# SCH_ESP32-S3-WROOM-RadioGateway-v1_0_202.net
KiCad netlist of a schematic drawn in EasyEDA
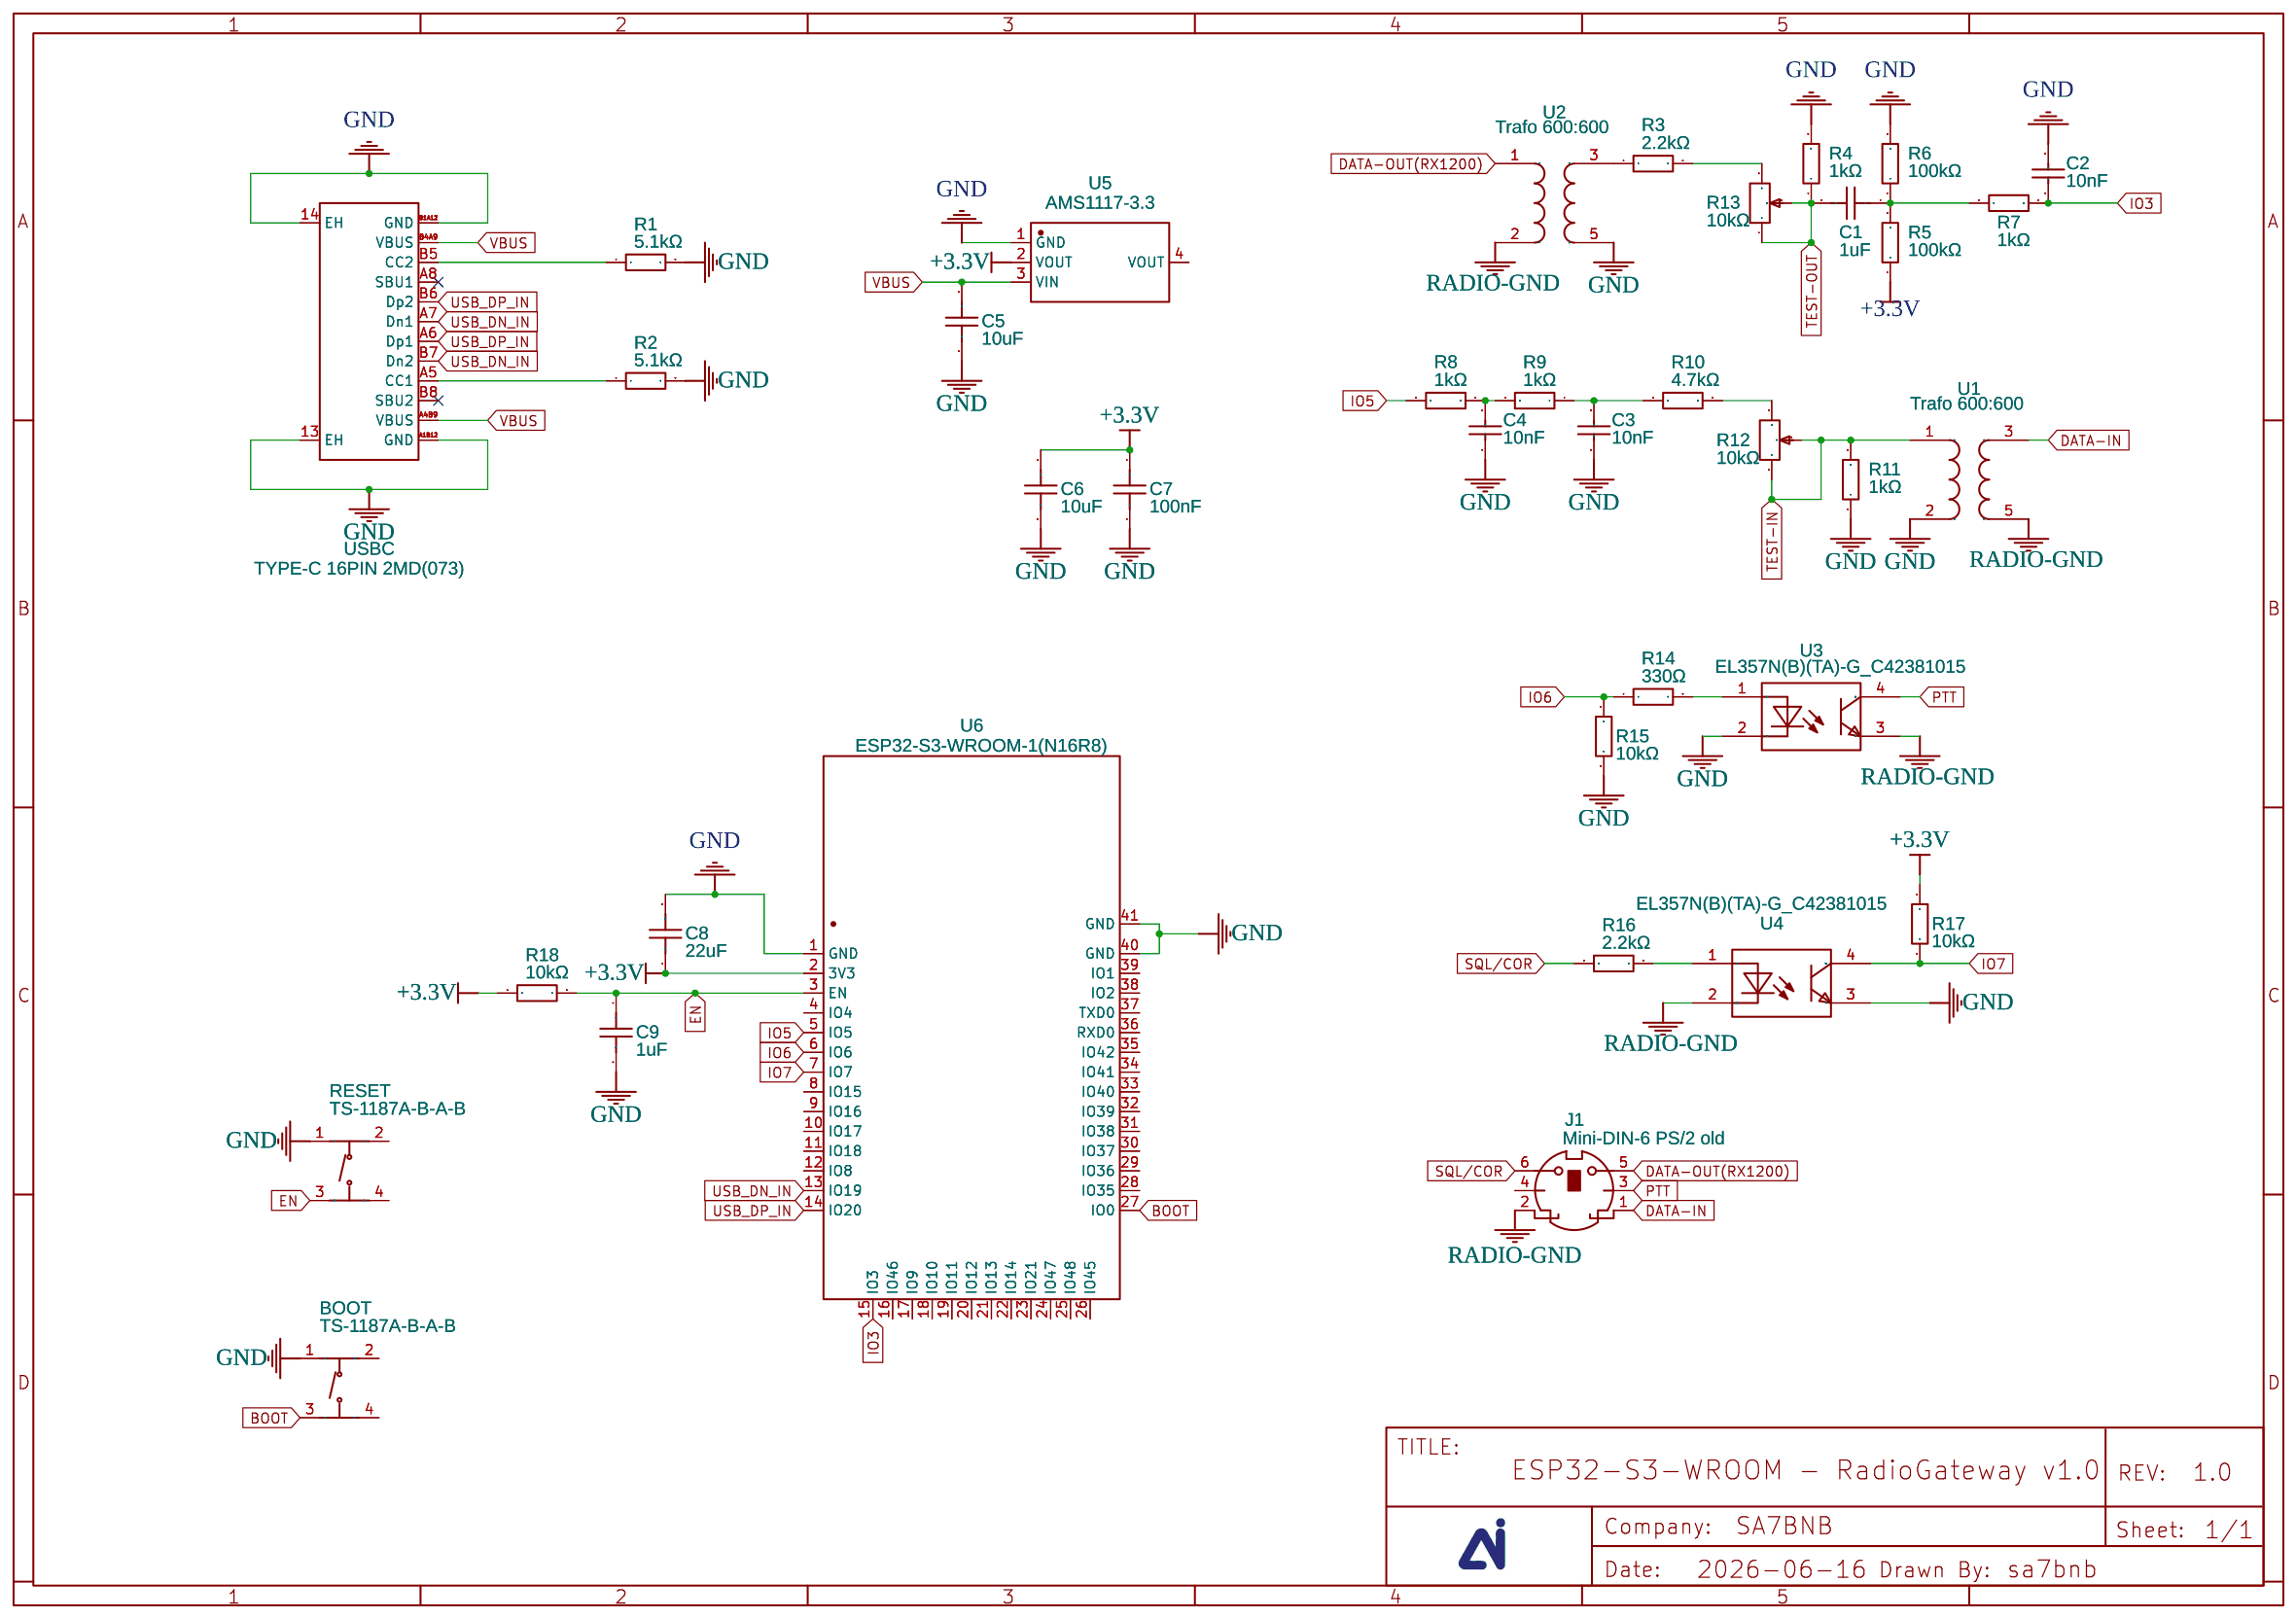
[diagram p0: schematic sheet]

(export (version "E")
  (design (tool "Eeschema 10.0.6"))
  (components
    (comp (ref "BOOT")
      (value "TS-1187A-B-A-B")
      (fields (field (name "Manufacturer") "XKB Connection(中国星坤)"))
      (libsource (lib "") (part "TS-1187A-B-A-B"))
    )
    (comp (ref "C1")
      (value "1uF")
      (fields
        (field (name "Manufacturer Part") "CL05A105KA5NQNC")
        (field (name "Manufacturer") "SAMSUNG(三星)")
      )
      (libsource (lib "") (part "CL05A105KA5NQNC"))
    )
    (comp (ref "C2")
      (value "10nF")
      (fields
        (field (name "Manufacturer Part") "CL05B103KB5NNNC")
        (field (name "Manufacturer") "SAMSUNG(三星)")
      )
      (libsource (lib "") (part "CL05B103KB5NNNC"))
    )
    (comp (ref "C3")
      (value "10nF")
      (fields
        (field (name "Manufacturer Part") "CL05B103KB5NNNC")
        (field (name "Manufacturer") "SAMSUNG(三星)")
      )
      (libsource (lib "") (part "CL05B103KB5NNNC"))
    )
    (comp (ref "C4")
      (value "10nF")
      (fields
        (field (name "Manufacturer Part") "CL05B103KB5NNNC")
        (field (name "Manufacturer") "SAMSUNG(三星)")
      )
      (libsource (lib "") (part "CL05B103KB5NNNC"))
    )
    (comp (ref "C5")
      (value "10uF")
      (fields
        (field (name "Manufacturer Part") "CL10A106KP8NNNC")
        (field (name "Manufacturer") "SAMSUNG(三星)")
      )
      (libsource (lib "") (part "CL10A106KP8NNNC_1"))
    )
    (comp (ref "C6")
      (value "10uF")
      (fields
        (field (name "Manufacturer Part") "CL10A106KP8NNNC")
        (field (name "Manufacturer") "SAMSUNG(三星)")
      )
      (libsource (lib "") (part "CL10A106KP8NNNC"))
    )
    (comp (ref "C7")
      (value "100nF")
      (fields
        (field (name "Manufacturer Part") "CL05B104KO5NNNC")
        (field (name "Manufacturer") "SAMSUNG(三星)")
      )
      (libsource (lib "") (part "CL05B104KO5NNNC"))
    )
    (comp (ref "C8")
      (value "22uF")
      (fields
        (field (name "Manufacturer Part") "CL21A226MAQNNNE")
        (field (name "Manufacturer") "SAMSUNG(三星)")
      )
      (libsource (lib "") (part "CL21A226MAQNNNE"))
    )
    (comp (ref "C9")
      (value "1uF")
      (fields
        (field (name "Manufacturer Part") "CL05A105KA5NQNC")
        (field (name "Manufacturer") "SAMSUNG(三星)")
      )
      (libsource (lib "") (part "CL05A105KA5NQNC_1"))
    )
    (comp (ref "J1") (value "Mini-DIN-6 PS/2 old") (libsource (lib "") (part "Mini-DIN-6 PS/2 old")))
    (comp (ref "R1")
      (value "5.1kΩ")
      (fields
        (field (name "Manufacturer Part") "0402WGF5101TCE")
        (field (name "Manufacturer") "UNI-ROYAL(厚声)")
      )
      (libsource (lib "") (part "0402WGF5101TCE"))
    )
    (comp (ref "R2")
      (value "5.1kΩ")
      (fields
        (field (name "Manufacturer Part") "0402WGF5101TCE")
        (field (name "Manufacturer") "UNI-ROYAL(厚声)")
      )
      (libsource (lib "") (part "0402WGF5101TCE"))
    )
    (comp (ref "R3")
      (value "2.2kΩ")
      (fields
        (field (name "Manufacturer Part") "0402WGF2201TCE")
        (field (name "Manufacturer") "UNI-ROYAL(厚声)")
      )
      (libsource (lib "") (part "0402WGF2201TCE"))
    )
    (comp (ref "R4")
      (value "1kΩ")
      (fields
        (field (name "Manufacturer Part") "0402WGF1001TCE")
        (field (name "Manufacturer") "UNI-ROYAL(厚声)")
      )
      (libsource (lib "") (part "0402WGF1001TCE_2"))
    )
    (comp (ref "R5")
      (value "100kΩ")
      (fields
        (field (name "Manufacturer Part") "0402WGF1003TCE")
        (field (name "Manufacturer") "UNI-ROYAL(厚声)")
      )
      (libsource (lib "") (part "0402WGF1003TCE"))
    )
    (comp (ref "R6")
      (value "100kΩ")
      (fields
        (field (name "Manufacturer Part") "0402WGF1003TCE")
        (field (name "Manufacturer") "UNI-ROYAL(厚声)")
      )
      (libsource (lib "") (part "0402WGF1003TCE"))
    )
    (comp (ref "R7")
      (value "1kΩ")
      (fields
        (field (name "Manufacturer Part") "0402WGF1001TCE")
        (field (name "Manufacturer") "UNI-ROYAL(厚声)")
      )
      (libsource (lib "") (part "0402WGF1001TCE_1"))
    )
    (comp (ref "R8")
      (value "1kΩ")
      (fields
        (field (name "Manufacturer Part") "0402WGF1001TCE")
        (field (name "Manufacturer") "UNI-ROYAL(厚声)")
      )
      (libsource (lib "") (part "0402WGF1001TCE"))
    )
    (comp (ref "R9")
      (value "1kΩ")
      (fields
        (field (name "Manufacturer Part") "0402WGF1001TCE")
        (field (name "Manufacturer") "UNI-ROYAL(厚声)")
      )
      (libsource (lib "") (part "0402WGF1001TCE"))
    )
    (comp (ref "R10")
      (value "4.7kΩ")
      (fields
        (field (name "Manufacturer Part") "0402WGF4701TCE")
        (field (name "Manufacturer") "UNI-ROYAL(厚声)")
      )
      (libsource (lib "") (part "0402WGF4701TCE"))
    )
    (comp (ref "R11")
      (value "1kΩ")
      (fields
        (field (name "Manufacturer Part") "0402WGF1001TCE")
        (field (name "Manufacturer") "UNI-ROYAL(厚声)")
      )
      (libsource (lib "") (part "0402WGF1001TCE_2"))
    )
    (comp (ref "R12")
      (value "10kΩ")
      (fields (field (name "Manufacturer Part") "3296W-1-103LF") (field (name "Manufacturer") "BOURNS"))
      (libsource (lib "") (part "3296W-1-103LF"))
    )
    (comp (ref "R13")
      (value "10kΩ")
      (fields (field (name "Manufacturer Part") "3296W-1-103LF") (field (name "Manufacturer") "BOURNS"))
      (libsource (lib "") (part "3296W-1-103LF"))
    )
    (comp (ref "R14")
      (value "330Ω")
      (fields
        (field (name "Manufacturer Part") "0402WGF3300TCE")
        (field (name "Manufacturer") "UNI-ROYAL(厚声)")
      )
      (libsource (lib "") (part "0402WGF3300TCE"))
    )
    (comp (ref "R15")
      (value "10kΩ")
      (fields
        (field (name "Manufacturer Part") "0402WGF1002TCE")
        (field (name "Manufacturer") "UNI-ROYAL(厚声)")
      )
      (libsource (lib "") (part "0402WGF1002TCE"))
    )
    (comp (ref "R16")
      (value "2.2kΩ")
      (fields
        (field (name "Manufacturer Part") "0402WGF2201TCE")
        (field (name "Manufacturer") "UNI-ROYAL(厚声)")
      )
      (libsource (lib "") (part "0402WGF2201TCE"))
    )
    (comp (ref "R17")
      (value "10kΩ")
      (fields
        (field (name "Manufacturer Part") "0402WGF1002TCE")
        (field (name "Manufacturer") "UNI-ROYAL(厚声)")
      )
      (libsource (lib "") (part "0402WGF1002TCE"))
    )
    (comp (ref "R18")
      (value "10kΩ")
      (fields
        (field (name "Manufacturer Part") "0402WGF1002TCE")
        (field (name "Manufacturer") "UNI-ROYAL(厚声)")
      )
      (libsource (lib "") (part "0402WGF1002TCE_1"))
    )
    (comp (ref "RESET")
      (value "TS-1187A-B-A-B")
      (fields (field (name "Manufacturer") "XKB Connection(中国星坤)"))
      (libsource (lib "") (part "TS-1187A-B-A-B_1"))
    )
    (comp (ref "U1")
      (value "Trafo 600:600")
      (fields (field (name "Manufacturer") "YongYeTai"))
      (libsource (lib "") (part "eduardo"))
    )
    (comp (ref "U2")
      (value "Trafo 600:600")
      (fields (field (name "Manufacturer") "YongYeTai"))
      (libsource (lib "") (part "eduardo"))
    )
    (comp (ref "U3")
      (value "EL357N(B)(TA)-G_C42381015")
      (fields
        (field (name "Manufacturer Part") "EL357N(B)(TA)-G")
        (field (name "Manufacturer") "EVERLIGHT(亿光)")
      )
      (libsource (lib "") (part "EL357N(B)(TA)-G_C42381015"))
    )
    (comp (ref "U4")
      (value "EL357N(B)(TA)-G_C42381015")
      (fields
        (field (name "Manufacturer Part") "EL357N(B)(TA)-G")
        (field (name "Manufacturer") "EVERLIGHT(亿光)")
      )
      (libsource (lib "") (part "EL357N(B)(TA)-G_C42381015"))
    )
    (comp (ref "U5")
      (value "AMS1117-3.3")
      (fields (field (name "Manufacturer") "Advanced Monolithic Systems"))
      (libsource (lib "") (part "AMS1117-3.3"))
    )
    (comp (ref "U6")
      (value "ESP32-S3-WROOM-1(N16R8)")
      (fields
        (field (name "Manufacturer Part") "ESP32-S3-WROOM-1-N16R8")
        (field (name "Manufacturer") "ESPRESSIF(乐鑫)")
      )
      (libsource (lib "") (part "ESP32-S3-WROOM-1(N16R8)"))
    )
    (comp (ref "USBC")
      (value "TYPE-C 16PIN 2MD(073)")
      (fields (field (name "Manufacturer") "SHOU HAN(首韩)"))
      (libsource (lib "") (part "TYPE-C 16PIN 2MD(073)"))
    )
  )
  (nets
    (net (code "1") (name "+3.3V") (class "Default")
      (node (ref "C6") (pin "1") (pinfunction "1_1") (pintype "unspecified"))
      (node (ref "C7") (pin "1") (pinfunction "1_1") (pintype "unspecified"))
      (node (ref "C8") (pin "1") (pinfunction "1_1") (pintype "unspecified"))
      (node (ref "R17") (pin "1") (pinfunction "1_1") (pintype "input"))
      (node (ref "R18") (pin "1") (pinfunction "1_1") (pintype "input"))
      (node (ref "R5") (pin "1") (pinfunction "1_1") (pintype "input"))
      (node (ref "U5") (pin "2") (pinfunction "VOUT_2") (pintype "unspecified"))
      (node (ref "U6") (pin "2") (pinfunction "3V3_2") (pintype "unspecified"))
    )
    (net (code "2") (name "BOOT") (class "Default")
      (node (ref "BOOT") (pin "3") (pinfunction "C_3") (pintype "unspecified"))
      (node (ref "U6") (pin "27") (pinfunction "IO0_27") (pintype "unspecified"))
    )
    (net (code "3") (name "DATA-IN") (class "Default")
      (node (ref "J1") (pin "1") (pintype "unspecified"))
      (node (ref "U1") (pin "3") (pinfunction "3_3") (pintype "unspecified"))
    )
    (net (code "4") (name "DATA-OUT(RX1200)") (class "Default")
      (node (ref "J1") (pin "5") (pintype "unspecified"))
      (node (ref "U2") (pin "1") (pinfunction "1_1") (pintype "unspecified"))
    )
    (net (code "5") (name "EN") (class "Default")
      (node (ref "C9") (pin "1") (pinfunction "1_1") (pintype "unspecified"))
      (node (ref "R18") (pin "2") (pinfunction "2_2") (pintype "input"))
      (node (ref "RESET") (pin "3") (pinfunction "C_3") (pintype "unspecified"))
      (node (ref "U6") (pin "3") (pinfunction "EN_3") (pintype "unspecified"))
    )
    (net (code "6") (name "GND") (class "Default")
      (node (ref "BOOT") (pin "1") (pinfunction "A_1") (pintype "unspecified"))
      (node (ref "C2") (pin "2") (pinfunction "2_2") (pintype "input"))
      (node (ref "C3") (pin "1") (pinfunction "1_1") (pintype "input"))
      (node (ref "C4") (pin "1") (pinfunction "1_1") (pintype "input"))
      (node (ref "C5") (pin "1") (pinfunction "1_1") (pintype "unspecified"))
      (node (ref "C6") (pin "2") (pinfunction "2_2") (pintype "unspecified"))
      (node (ref "C7") (pin "2") (pinfunction "2_2") (pintype "unspecified"))
      (node (ref "C8") (pin "2") (pinfunction "2_2") (pintype "unspecified"))
      (node (ref "C9") (pin "2") (pinfunction "2_2") (pintype "unspecified"))
      (node (ref "R1") (pin "2") (pinfunction "2_2") (pintype "input"))
      (node (ref "R11") (pin "1") (pinfunction "1_1") (pintype "input"))
      (node (ref "R15") (pin "2") (pinfunction "2_2") (pintype "input"))
      (node (ref "R2") (pin "2") (pinfunction "2_2") (pintype "input"))
      (node (ref "R4") (pin "2") (pinfunction "2_2") (pintype "input"))
      (node (ref "R6") (pin "2") (pinfunction "2_2") (pintype "input"))
      (node (ref "RESET") (pin "1") (pinfunction "A_1") (pintype "unspecified"))
      (node (ref "U1") (pin "2") (pinfunction "2_2") (pintype "unspecified"))
      (node (ref "U2") (pin "5") (pinfunction "5_5") (pintype "unspecified"))
      (node (ref "U3") (pin "2") (pinfunction "CAT_2") (pintype "unspecified"))
      (node (ref "U4") (pin "3") (pinfunction "EM_3") (pintype "unspecified"))
      (node (ref "U5") (pin "1") (pinfunction "GND_1") (pintype "unspecified"))
      (node (ref "U6") (pin "1") (pinfunction "GND_1") (pintype "unspecified"))
      (node (ref "U6") (pin "40") (pinfunction "GND_40") (pintype "unspecified"))
      (node (ref "U6") (pin "41") (pinfunction "GND_41") (pintype "unspecified"))
      (node (ref "USBC") (pin "13") (pinfunction "EH_13") (pintype "unspecified"))
      (node (ref "USBC") (pin "14") (pinfunction "EH_14") (pintype "unspecified"))
      (node (ref "USBC") (pin "A1B12") (pinfunction "GND_A1B12") (pintype "unspecified"))
      (node (ref "USBC") (pin "B1A12") (pinfunction "GND_B1A12") (pintype "unspecified"))
    )
    (net (code "7") (name "IO3") (class "Default")
      (node (ref "C2") (pin "1") (pinfunction "1_1") (pintype "input"))
      (node (ref "R7") (pin "2") (pinfunction "2_2") (pintype "input"))
      (node (ref "U6") (pin "15") (pinfunction "IO3_15") (pintype "unspecified"))
    )
    (net (code "8") (name "IO5") (class "Default")
      (node (ref "R8") (pin "2") (pinfunction "2_2") (pintype "input"))
      (node (ref "U6") (pin "5") (pinfunction "IO5_5") (pintype "unspecified"))
    )
    (net (code "9") (name "IO6") (class "Default")
      (node (ref "R14") (pin "1") (pinfunction "1_1") (pintype "input"))
      (node (ref "R15") (pin "1") (pinfunction "1_1") (pintype "input"))
      (node (ref "U6") (pin "6") (pinfunction "IO6_6") (pintype "unspecified"))
    )
    (net (code "10") (name "IO7") (class "Default")
      (node (ref "R17") (pin "2") (pinfunction "2_2") (pintype "input"))
      (node (ref "U4") (pin "4") (pinfunction "COL_4") (pintype "unspecified"))
      (node (ref "U6") (pin "7") (pinfunction "IO7_7") (pintype "unspecified"))
    )
    (net (code "11") (name "Net-(C1-Pad1)") (class "Default")
      (node (ref "C1") (pin "1") (pinfunction "1_1") (pintype "unspecified"))
      (node (ref "R5") (pin "2") (pinfunction "2_2") (pintype "input"))
      (node (ref "R6") (pin "1") (pinfunction "1_1") (pintype "input"))
      (node (ref "R7") (pin "1") (pinfunction "1_1") (pintype "input"))
    )
    (net (code "12") (name "Net-(C3-Pad2)") (class "Default")
      (node (ref "C3") (pin "2") (pinfunction "2_2") (pintype "input"))
      (node (ref "R10") (pin "1") (pinfunction "1_1") (pintype "input"))
      (node (ref "R9") (pin "1") (pinfunction "1_1") (pintype "input"))
    )
    (net (code "13") (name "Net-(C4-Pad2)") (class "Default")
      (node (ref "C4") (pin "2") (pinfunction "2_2") (pintype "input"))
      (node (ref "R8") (pin "1") (pinfunction "1_1") (pintype "input"))
      (node (ref "R9") (pin "2") (pinfunction "2_2") (pintype "input"))
    )
    (net (code "14") (name "Net-(R3-Pad1)") (class "Default")
      (node (ref "R3") (pin "1") (pinfunction "1_1") (pintype "input"))
      (node (ref "U2") (pin "3") (pinfunction "3_3") (pintype "unspecified"))
    )
    (net (code "15") (name "Net-(R10-Pad2)") (class "Default")
      (node (ref "R10") (pin "2") (pinfunction "2_2") (pintype "input"))
      (node (ref "R12") (pin "3") (pinfunction "3_3") (pintype "input"))
    )
    (net (code "16") (name "Net-(R13-Pad3)") (class "Default")
      (node (ref "R13") (pin "3") (pinfunction "3_3") (pintype "input"))
      (node (ref "R3") (pin "2") (pinfunction "2_2") (pintype "input"))
    )
    (net (code "17") (name "Net-(U3-AN)") (class "Default")
      (node (ref "R14") (pin "2") (pinfunction "2_2") (pintype "input"))
      (node (ref "U3") (pin "1") (pinfunction "AN_1") (pintype "unspecified"))
    )
    (net (code "18") (name "Net-(U4-AN)") (class "Default")
      (node (ref "R16") (pin "2") (pinfunction "2_2") (pintype "input"))
      (node (ref "U4") (pin "1") (pinfunction "AN_1") (pintype "unspecified"))
    )
    (net (code "19") (name "Net-(USBC-CC1)") (class "Default")
      (node (ref "R2") (pin "1") (pinfunction "1_1") (pintype "input"))
      (node (ref "USBC") (pin "A5") (pinfunction "CC1_A5") (pintype "unspecified"))
    )
    (net (code "20") (name "Net-(USBC-CC2)") (class "Default")
      (node (ref "R1") (pin "1") (pinfunction "1_1") (pintype "input"))
      (node (ref "USBC") (pin "B5") (pinfunction "CC2_B5") (pintype "unspecified"))
    )
    (net (code "21") (name "PTT") (class "Default")
      (node (ref "J1") (pin "3") (pintype "unspecified"))
      (node (ref "U3") (pin "4") (pinfunction "COL_4") (pintype "unspecified"))
    )
    (net (code "22") (name "RADIO-GND") (class "Default")
      (node (ref "J1") (pin "2") (pintype "unspecified"))
      (node (ref "U1") (pin "5") (pinfunction "5_5") (pintype "unspecified"))
      (node (ref "U2") (pin "2") (pinfunction "2_2") (pintype "unspecified"))
      (node (ref "U3") (pin "3") (pinfunction "EM_3") (pintype "unspecified"))
      (node (ref "U4") (pin "2") (pinfunction "CAT_2") (pintype "unspecified"))
    )
    (net (code "23") (name "SQL{slash}COR") (class "Default")
      (node (ref "J1") (pin "6") (pintype "unspecified"))
      (node (ref "R16") (pin "1") (pinfunction "1_1") (pintype "input"))
    )
    (net (code "24") (name "TEST-IN") (class "Default")
      (node (ref "R11") (pin "2") (pinfunction "2_2") (pintype "input"))
      (node (ref "R12") (pin "1") (pinfunction "1_1") (pintype "input"))
      (node (ref "R12") (pin "2") (pinfunction "2_2") (pintype "input"))
      (node (ref "U1") (pin "1") (pinfunction "1_1") (pintype "unspecified"))
    )
    (net (code "25") (name "TEST-OUT") (class "Default")
      (node (ref "C1") (pin "2") (pinfunction "2_2") (pintype "unspecified"))
      (node (ref "R13") (pin "1") (pinfunction "1_1") (pintype "input"))
      (node (ref "R13") (pin "2") (pinfunction "2_2") (pintype "input"))
      (node (ref "R4") (pin "1") (pinfunction "1_1") (pintype "input"))
    )
    (net (code "26") (name "USB_DN_IN") (class "Default")
      (node (ref "U6") (pin "13") (pinfunction "IO19_13") (pintype "unspecified"))
      (node (ref "USBC") (pin "A7") (pinfunction "Dn1_A7") (pintype "unspecified"))
      (node (ref "USBC") (pin "B7") (pinfunction "Dn2_B7") (pintype "unspecified"))
    )
    (net (code "27") (name "USB_DP_IN") (class "Default")
      (node (ref "U6") (pin "14") (pinfunction "IO20_14") (pintype "unspecified"))
      (node (ref "USBC") (pin "A6") (pinfunction "Dp1_A6") (pintype "unspecified"))
      (node (ref "USBC") (pin "B6") (pinfunction "Dp2_B6") (pintype "unspecified"))
    )
    (net (code "28") (name "VBUS") (class "Default")
      (node (ref "C5") (pin "2") (pinfunction "2_2") (pintype "unspecified"))
      (node (ref "U5") (pin "3") (pinfunction "VIN_3") (pintype "unspecified"))
      (node (ref "USBC") (pin "A4B9") (pinfunction "VBUS_A4B9") (pintype "unspecified"))
      (node (ref "USBC") (pin "B4A9") (pinfunction "VBUS_B4A9") (pintype "unspecified"))
    )
    (net (code "29") (name "unconnected-(BOOT-B-Pad2)") (class "Default")
      (node (ref "BOOT") (pin "2") (pinfunction "B_2") (pintype "unspecified"))
    )
    (net (code "30") (name "unconnected-(BOOT-D-Pad4)") (class "Default")
      (node (ref "BOOT") (pin "4") (pinfunction "D_4") (pintype "unspecified"))
    )
    (net (code "31") (name "unconnected-(J1-Pad4)") (class "Default")
      (node (ref "J1") (pin "4") (pintype "unspecified"))
    )
    (net (code "32") (name "unconnected-(RESET-B-Pad2)") (class "Default")
      (node (ref "RESET") (pin "2") (pinfunction "B_2") (pintype "unspecified"))
    )
    (net (code "33") (name "unconnected-(RESET-D-Pad4)") (class "Default")
      (node (ref "RESET") (pin "4") (pinfunction "D_4") (pintype "unspecified"))
    )
    (net (code "34") (name "unconnected-(U5-VOUT-Pad4)") (class "Default")
      (node (ref "U5") (pin "4") (pinfunction "VOUT_4") (pintype "unspecified"))
    )
    (net (code "35") (name "unconnected-(U6-IO1-Pad39)") (class "Default")
      (node (ref "U6") (pin "39") (pinfunction "IO1_39") (pintype "unspecified"))
    )
    (net (code "36") (name "unconnected-(U6-IO2-Pad38)") (class "Default")
      (node (ref "U6") (pin "38") (pinfunction "IO2_38") (pintype "unspecified"))
    )
    (net (code "37") (name "unconnected-(U6-IO4-Pad4)") (class "Default")
      (node (ref "U6") (pin "4") (pinfunction "IO4_4") (pintype "unspecified"))
    )
    (net (code "38") (name "unconnected-(U6-IO8-Pad12)") (class "Default")
      (node (ref "U6") (pin "12") (pinfunction "IO8_12") (pintype "unspecified"))
    )
    (net (code "39") (name "unconnected-(U6-IO9-Pad17)") (class "Default")
      (node (ref "U6") (pin "17") (pinfunction "IO9_17") (pintype "unspecified"))
    )
    (net (code "40") (name "unconnected-(U6-IO10-Pad18)") (class "Default")
      (node (ref "U6") (pin "18") (pinfunction "IO10_18") (pintype "unspecified"))
    )
    (net (code "41") (name "unconnected-(U6-IO11-Pad19)") (class "Default")
      (node (ref "U6") (pin "19") (pinfunction "IO11_19") (pintype "unspecified"))
    )
    (net (code "42") (name "unconnected-(U6-IO12-Pad20)") (class "Default")
      (node (ref "U6") (pin "20") (pinfunction "IO12_20") (pintype "unspecified"))
    )
    (net (code "43") (name "unconnected-(U6-IO13-Pad21)") (class "Default")
      (node (ref "U6") (pin "21") (pinfunction "IO13_21") (pintype "unspecified"))
    )
    (net (code "44") (name "unconnected-(U6-IO14-Pad22)") (class "Default")
      (node (ref "U6") (pin "22") (pinfunction "IO14_22") (pintype "unspecified"))
    )
    (net (code "45") (name "unconnected-(U6-IO15-Pad8)") (class "Default")
      (node (ref "U6") (pin "8") (pinfunction "IO15_8") (pintype "unspecified"))
    )
    (net (code "46") (name "unconnected-(U6-IO16-Pad9)") (class "Default")
      (node (ref "U6") (pin "9") (pinfunction "IO16_9") (pintype "unspecified"))
    )
    (net (code "47") (name "unconnected-(U6-IO17-Pad10)") (class "Default")
      (node (ref "U6") (pin "10") (pinfunction "IO17_10") (pintype "unspecified"))
    )
    (net (code "48") (name "unconnected-(U6-IO18-Pad11)") (class "Default")
      (node (ref "U6") (pin "11") (pinfunction "IO18_11") (pintype "unspecified"))
    )
    (net (code "49") (name "unconnected-(U6-IO21-Pad23)") (class "Default")
      (node (ref "U6") (pin "23") (pinfunction "IO21_23") (pintype "unspecified"))
    )
    (net (code "50") (name "unconnected-(U6-IO35-Pad28)") (class "Default")
      (node (ref "U6") (pin "28") (pinfunction "IO35_28") (pintype "unspecified"))
    )
    (net (code "51") (name "unconnected-(U6-IO36-Pad29)") (class "Default")
      (node (ref "U6") (pin "29") (pinfunction "IO36_29") (pintype "unspecified"))
    )
    (net (code "52") (name "unconnected-(U6-IO37-Pad30)") (class "Default")
      (node (ref "U6") (pin "30") (pinfunction "IO37_30") (pintype "unspecified"))
    )
    (net (code "53") (name "unconnected-(U6-IO38-Pad31)") (class "Default")
      (node (ref "U6") (pin "31") (pinfunction "IO38_31") (pintype "unspecified"))
    )
    (net (code "54") (name "unconnected-(U6-IO39-Pad32)") (class "Default")
      (node (ref "U6") (pin "32") (pinfunction "IO39_32") (pintype "unspecified"))
    )
    (net (code "55") (name "unconnected-(U6-IO40-Pad33)") (class "Default")
      (node (ref "U6") (pin "33") (pinfunction "IO40_33") (pintype "unspecified"))
    )
    (net (code "56") (name "unconnected-(U6-IO41-Pad34)") (class "Default")
      (node (ref "U6") (pin "34") (pinfunction "IO41_34") (pintype "unspecified"))
    )
    (net (code "57") (name "unconnected-(U6-IO42-Pad35)") (class "Default")
      (node (ref "U6") (pin "35") (pinfunction "IO42_35") (pintype "unspecified"))
    )
    (net (code "58") (name "unconnected-(U6-IO45-Pad26)") (class "Default")
      (node (ref "U6") (pin "26") (pinfunction "IO45_26") (pintype "unspecified"))
    )
    (net (code "59") (name "unconnected-(U6-IO46-Pad16)") (class "Default")
      (node (ref "U6") (pin "16") (pinfunction "IO46_16") (pintype "unspecified"))
    )
    (net (code "60") (name "unconnected-(U6-IO47-Pad24)") (class "Default")
      (node (ref "U6") (pin "24") (pinfunction "IO47_24") (pintype "unspecified"))
    )
    (net (code "61") (name "unconnected-(U6-IO48-Pad25)") (class "Default")
      (node (ref "U6") (pin "25") (pinfunction "IO48_25") (pintype "unspecified"))
    )
    (net (code "62") (name "unconnected-(U6-RXD0-Pad36)") (class "Default")
      (node (ref "U6") (pin "36") (pinfunction "RXD0_36") (pintype "unspecified"))
    )
    (net (code "63") (name "unconnected-(U6-TXD0-Pad37)") (class "Default")
      (node (ref "U6") (pin "37") (pinfunction "TXD0_37") (pintype "unspecified"))
    )
    (net (code "64") (name "unconnected-(USBC-SBU1-PadA8)") (class "Default")
      (node (ref "USBC") (pin "A8") (pinfunction "SBU1_A8") (pintype "unspecified+no_connect"))
    )
    (net (code "65") (name "unconnected-(USBC-SBU2-PadB8)") (class "Default")
      (node (ref "USBC") (pin "B8") (pinfunction "SBU2_B8") (pintype "unspecified+no_connect"))
    )
  )
)
